# Proximity_module.net
KiCad netlist of a schematic drawn in EAGLE
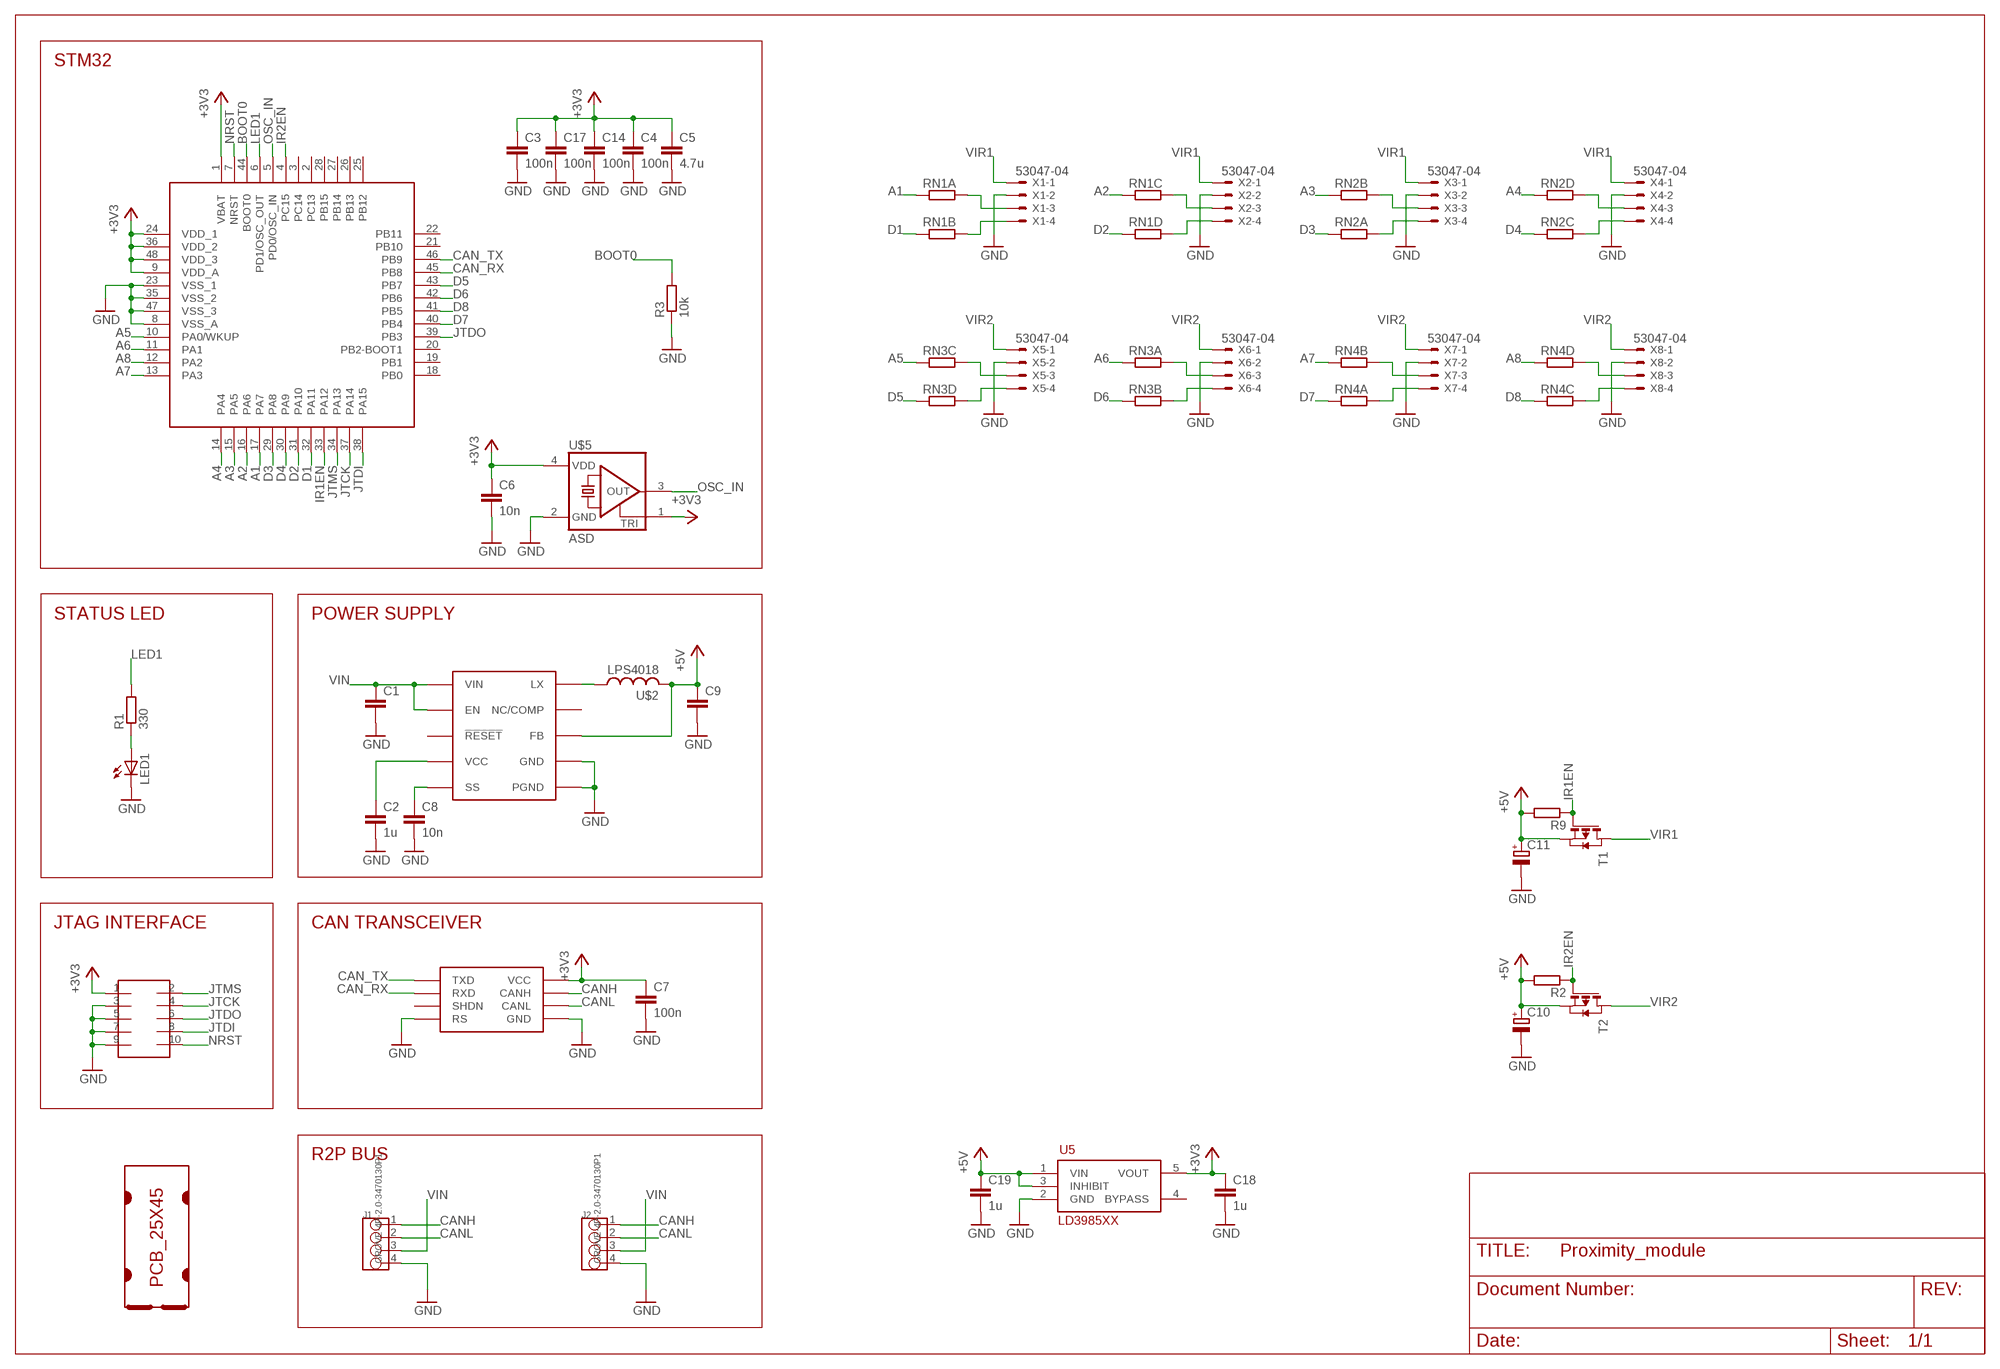
[diagram p0: schematic, sheet 1]

(export (version "E")
  (design (tool "Eeschema 10.0.6"))
  (components
    (comp (ref "C1")
      (value "C-EUC1206")
      (footprint "eagle-import:C1206")
      (libsource (lib "eagle-import") (part "C-EUC1206"))
    )
    (comp (ref "C2")
      (value "1u")
      (footprint "eagle-import:C0603")
      (libsource (lib "eagle-import") (part "C-EUC0603"))
    )
    (comp (ref "C3")
      (value "100n")
      (footprint "eagle-import:C0603")
      (libsource (lib "eagle-import") (part "C-EUC0603"))
    )
    (comp (ref "C4")
      (value "100n")
      (footprint "eagle-import:C0603")
      (libsource (lib "eagle-import") (part "C-EUC0603"))
    )
    (comp (ref "C5")
      (value "4.7u")
      (footprint "eagle-import:C0805")
      (libsource (lib "eagle-import") (part "C-EUC0805"))
    )
    (comp (ref "C6")
      (value "10n")
      (footprint "eagle-import:C0603")
      (libsource (lib "eagle-import") (part "C-EUC0603"))
    )
    (comp (ref "C7")
      (value "100n")
      (footprint "eagle-import:C0603")
      (libsource (lib "eagle-import") (part "C-EUC0603"))
    )
    (comp (ref "C8")
      (value "10n")
      (footprint "eagle-import:C0603")
      (libsource (lib "eagle-import") (part "C-EUC0603"))
    )
    (comp (ref "C9")
      (value "C-EUC0805")
      (footprint "eagle-import:C0805")
      (libsource (lib "eagle-import") (part "C-EUC0805"))
    )
    (comp (ref "C10")
      (value "CPOL-EUB/3528-21R")
      (footprint "eagle-import:B_3528-21R")
      (libsource (lib "eagle-import") (part "CPOL-EUB/3528-21R"))
    )
    (comp (ref "C11")
      (value "CPOL-EUB/3528-21R")
      (footprint "eagle-import:B_3528-21R")
      (libsource (lib "eagle-import") (part "CPOL-EUB/3528-21R"))
    )
    (comp (ref "C14")
      (value "100n")
      (footprint "eagle-import:C0603")
      (libsource (lib "eagle-import") (part "C-EUC0603"))
    )
    (comp (ref "C17")
      (value "100n")
      (footprint "eagle-import:C0603")
      (libsource (lib "eagle-import") (part "C-EUC0603"))
    )
    (comp (ref "C18")
      (value "1u")
      (footprint "eagle-import:C0603")
      (libsource (lib "eagle-import") (part "C-EUC0603"))
    )
    (comp (ref "C19")
      (value "1u")
      (footprint "eagle-import:C0603")
      (libsource (lib "eagle-import") (part "C-EUC0603"))
    )
    (comp (ref "J1")
      (value "GROVE-4P-2.0-3470130P1")
      (footprint "eagle-import:4P-2.0")
      (libsource (lib "eagle-import") (part "GROVE-4P-2.0-3470130P1"))
    )
    (comp (ref "J2")
      (value "GROVE-4P-2.0-3470130P1")
      (footprint "eagle-import:4P-2.0")
      (libsource (lib "eagle-import") (part "GROVE-4P-2.0-3470130P1"))
    )
    (comp (ref "LED1")
      (value "LEDCHIPLED_0805")
      (footprint "eagle-import:CHIPLED_0805")
      (libsource (lib "eagle-import") (part "LEDCHIPLED_0805"))
    )
    (comp (ref "R1")
      (value "330")
      (footprint "eagle-import:R0603")
      (libsource (lib "eagle-import") (part "R-EU_R0603"))
    )
    (comp (ref "R2")
      (value "R-EU_R0603")
      (footprint "eagle-import:R0603")
      (libsource (lib "eagle-import") (part "R-EU_R0603"))
    )
    (comp (ref "R3")
      (value "10k")
      (footprint "eagle-import:R0603")
      (libsource (lib "eagle-import") (part "R-EU_R0603"))
    )
    (comp (ref "R9")
      (value "R-EU_R0603")
      (footprint "eagle-import:R0603")
      (libsource (lib "eagle-import") (part "R-EU_R0603"))
    )
    (comp (ref "RN1")
      (value "RESISTOR_ARRAY_4")
      (footprint "eagle-import:RN8P-4R-CRA06S")
      (libsource (lib "eagle-import") (part "RESISTOR_ARRAY_4"))
    )
    (comp (ref "RN2")
      (value "RESISTOR_ARRAY_4")
      (footprint "eagle-import:RN8P-4R-CRA06S")
      (libsource (lib "eagle-import") (part "RESISTOR_ARRAY_4"))
    )
    (comp (ref "RN3")
      (value "RESISTOR_ARRAY_4")
      (footprint "eagle-import:RN8P-4R-CRA06S")
      (libsource (lib "eagle-import") (part "RESISTOR_ARRAY_4"))
    )
    (comp (ref "RN4")
      (value "RESISTOR_ARRAY_4")
      (footprint "eagle-import:RN8P-4R-CRA06S")
      (libsource (lib "eagle-import") (part "RESISTOR_ARRAY_4"))
    )
    (comp (ref "SOT1")
      (value "MAX3051EKA")
      (footprint "eagle-import:SOT23-8L")
      (libsource (lib "eagle-import") (part "MAX3051EKA"))
    )
    (comp (ref "T1")
      (value "PMOSSOT23")
      (footprint "eagle-import:SOT-23")
      (libsource (lib "eagle-import") (part "PMOSSOT23"))
    )
    (comp (ref "T2")
      (value "PMOSSOT23")
      (footprint "eagle-import:SOT-23")
      (libsource (lib "eagle-import") (part "PMOSSOT23"))
    )
    (comp (ref "U$1")
      (value "PCB_25X45")
      (footprint "eagle-import:25X45")
      (libsource (lib "eagle-import") (part "PCB_25X45"))
    )
    (comp (ref "U$2")
      (value "LPS4018")
      (footprint "eagle-import:LPS4018")
      (libsource (lib "eagle-import") (part "LPS4018"))
    )
    (comp (ref "U$3")
      (value "MAX17501")
      (footprint "eagle-import:TDFN-10")
      (libsource (lib "eagle-import") (part "MAX17501"))
    )
    (comp (ref "U$4")
      (value "FTSH-105TH")
      (footprint "eagle-import:FTSH-105-TH")
      (libsource (lib "eagle-import") (part "FTSH-105TH"))
    )
    (comp (ref "U$5")
      (value "ASD")
      (footprint "eagle-import:2.5X2")
      (libsource (lib "eagle-import") (part "ASD"))
    )
    (comp (ref "U$6")
      (value "STM32F103CXTX")
      (footprint "eagle-import:LQFP48")
      (libsource (lib "eagle-import") (part "STM32F103CXTX"))
    )
    (comp (ref "U5")
      (value "LD3985XX")
      (footprint "eagle-import:SOT23-5L")
      (libsource (lib "eagle-import") (part "LD3985XX"))
    )
    (comp (ref "X1")
      (value "53047-04")
      (footprint "eagle-import:53047-04")
      (fields (field (name "MF") "WALDOM/MOLEX") (field (name "MPN") "53047-0410"))
      (libsource (lib "eagle-import") (part "53?-04047"))
    )
    (comp (ref "X2")
      (value "53047-04")
      (footprint "eagle-import:53047-04")
      (fields (field (name "MF") "WALDOM/MOLEX") (field (name "MPN") "53047-0410"))
      (libsource (lib "eagle-import") (part "53?-04047"))
    )
    (comp (ref "X3")
      (value "53047-04")
      (footprint "eagle-import:53047-04")
      (fields (field (name "MF") "WALDOM/MOLEX") (field (name "MPN") "53047-0410"))
      (libsource (lib "eagle-import") (part "53?-04047"))
    )
    (comp (ref "X4")
      (value "53047-04")
      (footprint "eagle-import:53047-04")
      (fields (field (name "MF") "WALDOM/MOLEX") (field (name "MPN") "53047-0410"))
      (libsource (lib "eagle-import") (part "53?-04047"))
    )
    (comp (ref "X5")
      (value "53047-04")
      (footprint "eagle-import:53047-04")
      (fields (field (name "MF") "WALDOM/MOLEX") (field (name "MPN") "53047-0410"))
      (libsource (lib "eagle-import") (part "53?-04047"))
    )
    (comp (ref "X6")
      (value "53047-04")
      (footprint "eagle-import:53047-04")
      (fields (field (name "MF") "WALDOM/MOLEX") (field (name "MPN") "53047-0410"))
      (libsource (lib "eagle-import") (part "53?-04047"))
    )
    (comp (ref "X7")
      (value "53047-04")
      (footprint "eagle-import:53047-04")
      (fields (field (name "MF") "WALDOM/MOLEX") (field (name "MPN") "53047-0410"))
      (libsource (lib "eagle-import") (part "53?-04047"))
    )
    (comp (ref "X8")
      (value "53047-04")
      (footprint "eagle-import:53047-04")
      (fields (field (name "MF") "WALDOM/MOLEX") (field (name "MPN") "53047-0410"))
      (libsource (lib "eagle-import") (part "53?-04047"))
    )
  )
  (nets
    (net (code "1") (name "+3V3") (class "Default")
      (node (ref "C14") (pin "1") (pinfunction "1_1") (pintype "passive"))
      (node (ref "C17") (pin "1") (pinfunction "1_1") (pintype "passive"))
      (node (ref "C18") (pin "1") (pinfunction "1_1") (pintype "passive"))
      (node (ref "C3") (pin "1") (pinfunction "1_1") (pintype "passive"))
      (node (ref "C4") (pin "1") (pinfunction "1_1") (pintype "passive"))
      (node (ref "C5") (pin "1") (pinfunction "1_1") (pintype "passive"))
      (node (ref "C6") (pin "1") (pinfunction "1_1") (pintype "passive"))
      (node (ref "C7") (pin "1") (pinfunction "1_1") (pintype "passive"))
      (node (ref "SOT1") (pin "3") (pinfunction "VCC_3") (pintype "bidirectional"))
      (node (ref "U$4") (pin "1") (pinfunction "P$1_1") (pintype "bidirectional"))
      (node (ref "U$5") (pin "1") (pinfunction "TRI_1") (pintype "input"))
      (node (ref "U$5") (pin "4") (pinfunction "VDD_4") (pintype "power_in"))
      (node (ref "U$6") (pin "1") (pinfunction "VBAT_1") (pintype "bidirectional"))
      (node (ref "U$6") (pin "24") (pinfunction "VDD_1_24") (pintype "bidirectional"))
      (node (ref "U$6") (pin "36") (pinfunction "VDD_2_36") (pintype "bidirectional"))
      (node (ref "U$6") (pin "48") (pinfunction "VDD_3_48") (pintype "bidirectional"))
      (node (ref "U$6") (pin "9") (pinfunction "VDD_A_9") (pintype "bidirectional"))
      (node (ref "U5") (pin "5") (pinfunction "VOUT_5") (pintype "bidirectional"))
    )
    (net (code "2") (name "+5V") (class "Default")
      (node (ref "C10") (pin "+") (pinfunction "+_+") (pintype "passive"))
      (node (ref "C11") (pin "+") (pinfunction "+_+") (pintype "passive"))
      (node (ref "C19") (pin "1") (pinfunction "1_1") (pintype "passive"))
      (node (ref "C9") (pin "1") (pinfunction "1_1") (pintype "passive"))
      (node (ref "R2") (pin "2") (pinfunction "2_2") (pintype "passive"))
      (node (ref "R9") (pin "2") (pinfunction "2_2") (pintype "passive"))
      (node (ref "T1") (pin "2") (pinfunction "S_2") (pintype "passive"))
      (node (ref "T2") (pin "2") (pinfunction "S_2") (pintype "passive"))
      (node (ref "U$2") (pin "P$2") (pinfunction "2_P$2") (pintype "passive"))
      (node (ref "U$3") (pin "P$5") (pinfunction "FB_P$5") (pintype "bidirectional"))
      (node (ref "U5") (pin "1") (pinfunction "VIN_1") (pintype "bidirectional"))
      (node (ref "U5") (pin "3") (pinfunction "INHIBIT_3") (pintype "bidirectional"))
    )
    (net (code "3") (name "/A1") (class "Default")
      (node (ref "RN1") (pin "1") (pinfunction "1_1") (pintype "passive"))
      (node (ref "U$6") (pin "17") (pinfunction "PA7_17") (pintype "bidirectional"))
    )
    (net (code "4") (name "/A2") (class "Default")
      (node (ref "RN1") (pin "3") (pinfunction "1_3") (pintype "passive"))
      (node (ref "U$6") (pin "16") (pinfunction "PA6_16") (pintype "bidirectional"))
    )
    (net (code "5") (name "/A3") (class "Default")
      (node (ref "RN2") (pin "2") (pinfunction "1_2") (pintype "passive"))
      (node (ref "U$6") (pin "15") (pinfunction "PA5_15") (pintype "bidirectional"))
    )
    (net (code "6") (name "/A4") (class "Default")
      (node (ref "RN2") (pin "4") (pinfunction "1_4") (pintype "passive"))
      (node (ref "U$6") (pin "14") (pinfunction "PA4_14") (pintype "bidirectional"))
    )
    (net (code "7") (name "/A5") (class "Default")
      (node (ref "RN3") (pin "3") (pinfunction "1_3") (pintype "passive"))
      (node (ref "U$6") (pin "10") (pinfunction "PA0/WKUP_10") (pintype "bidirectional"))
    )
    (net (code "8") (name "/A6") (class "Default")
      (node (ref "RN3") (pin "1") (pinfunction "1_1") (pintype "passive"))
      (node (ref "U$6") (pin "11") (pinfunction "PA1_11") (pintype "bidirectional"))
    )
    (net (code "9") (name "/A7") (class "Default")
      (node (ref "RN4") (pin "2") (pinfunction "1_2") (pintype "passive"))
      (node (ref "U$6") (pin "13") (pinfunction "PA3_13") (pintype "bidirectional"))
    )
    (net (code "10") (name "/A8") (class "Default")
      (node (ref "RN4") (pin "4") (pinfunction "1_4") (pintype "passive"))
      (node (ref "U$6") (pin "12") (pinfunction "PA2_12") (pintype "bidirectional"))
    )
    (net (code "11") (name "/BOOT0") (class "Default")
      (node (ref "R3") (pin "2") (pinfunction "2_2") (pintype "passive"))
      (node (ref "U$6") (pin "44") (pinfunction "BOOT0_44") (pintype "bidirectional"))
    )
    (net (code "12") (name "/CANH") (class "Default")
      (node (ref "J1") (pin "1") (pinfunction "1_1") (pintype "bidirectional"))
      (node (ref "J2") (pin "1") (pinfunction "1_1") (pintype "bidirectional"))
      (node (ref "SOT1") (pin "7") (pinfunction "CANH_7") (pintype "bidirectional"))
    )
    (net (code "13") (name "/CANL") (class "Default")
      (node (ref "J1") (pin "2") (pinfunction "2_2") (pintype "bidirectional"))
      (node (ref "J2") (pin "2") (pinfunction "2_2") (pintype "bidirectional"))
      (node (ref "SOT1") (pin "6") (pinfunction "CANL_6") (pintype "bidirectional"))
    )
    (net (code "14") (name "/CAN_RX") (class "Default")
      (node (ref "SOT1") (pin "4") (pinfunction "RXD_4") (pintype "bidirectional"))
      (node (ref "U$6") (pin "45") (pinfunction "PB8_45") (pintype "bidirectional"))
    )
    (net (code "15") (name "/CAN_TX") (class "Default")
      (node (ref "SOT1") (pin "1") (pinfunction "TXD_1") (pintype "bidirectional"))
      (node (ref "U$6") (pin "46") (pinfunction "PB9_46") (pintype "bidirectional"))
    )
    (net (code "16") (name "/D1") (class "Default")
      (node (ref "RN1") (pin "2") (pinfunction "1_2") (pintype "passive"))
      (node (ref "U$6") (pin "32") (pinfunction "PA11_32") (pintype "bidirectional"))
    )
    (net (code "17") (name "/D2") (class "Default")
      (node (ref "RN1") (pin "4") (pinfunction "1_4") (pintype "passive"))
      (node (ref "U$6") (pin "31") (pinfunction "PA10_31") (pintype "bidirectional"))
    )
    (net (code "18") (name "/D3") (class "Default")
      (node (ref "RN2") (pin "1") (pinfunction "1_1") (pintype "passive"))
      (node (ref "U$6") (pin "29") (pinfunction "PA8_29") (pintype "bidirectional"))
    )
    (net (code "19") (name "/D4") (class "Default")
      (node (ref "RN2") (pin "3") (pinfunction "1_3") (pintype "passive"))
      (node (ref "U$6") (pin "30") (pinfunction "PA9_30") (pintype "bidirectional"))
    )
    (net (code "20") (name "/D5") (class "Default")
      (node (ref "RN3") (pin "4") (pinfunction "1_4") (pintype "passive"))
      (node (ref "U$6") (pin "43") (pinfunction "PB7_43") (pintype "bidirectional"))
    )
    (net (code "21") (name "/D6") (class "Default")
      (node (ref "RN3") (pin "2") (pinfunction "1_2") (pintype "passive"))
      (node (ref "U$6") (pin "42") (pinfunction "PB6_42") (pintype "bidirectional"))
    )
    (net (code "22") (name "/D7") (class "Default")
      (node (ref "RN4") (pin "1") (pinfunction "1_1") (pintype "passive"))
      (node (ref "U$6") (pin "40") (pinfunction "PB4_40") (pintype "bidirectional"))
    )
    (net (code "23") (name "/D8") (class "Default")
      (node (ref "RN4") (pin "3") (pinfunction "1_3") (pintype "passive"))
      (node (ref "U$6") (pin "41") (pinfunction "PB5_41") (pintype "bidirectional"))
    )
    (net (code "24") (name "/IR1EN") (class "Default")
      (node (ref "R9") (pin "1") (pinfunction "1_1") (pintype "passive"))
      (node (ref "T1") (pin "3") (pinfunction "G_3") (pintype "passive"))
      (node (ref "U$6") (pin "33") (pinfunction "PA12_33") (pintype "bidirectional"))
    )
    (net (code "25") (name "/IR2EN") (class "Default")
      (node (ref "R2") (pin "1") (pinfunction "1_1") (pintype "passive"))
      (node (ref "T2") (pin "3") (pinfunction "G_3") (pintype "passive"))
      (node (ref "U$6") (pin "4") (pinfunction "PC15_4") (pintype "bidirectional"))
    )
    (net (code "26") (name "/JTCK") (class "Default")
      (node (ref "U$4") (pin "4") (pinfunction "P$4_4") (pintype "bidirectional"))
      (node (ref "U$6") (pin "37") (pinfunction "PA14_37") (pintype "bidirectional"))
    )
    (net (code "27") (name "/JTDI") (class "Default")
      (node (ref "U$4") (pin "8") (pinfunction "P$8_8") (pintype "bidirectional"))
      (node (ref "U$6") (pin "38") (pinfunction "PA15_38") (pintype "bidirectional"))
    )
    (net (code "28") (name "/JTDO") (class "Default")
      (node (ref "U$4") (pin "6") (pinfunction "P$6_6") (pintype "bidirectional"))
      (node (ref "U$6") (pin "39") (pinfunction "PB3_39") (pintype "bidirectional"))
    )
    (net (code "29") (name "/JTMS") (class "Default")
      (node (ref "U$4") (pin "2") (pinfunction "P$2_2") (pintype "bidirectional"))
      (node (ref "U$6") (pin "34") (pinfunction "PA13_34") (pintype "bidirectional"))
    )
    (net (code "30") (name "/LED1") (class "Default")
      (node (ref "R1") (pin "2") (pinfunction "2_2") (pintype "passive"))
      (node (ref "U$6") (pin "6") (pinfunction "PD1/OSC_OUT_6") (pintype "bidirectional"))
    )
    (net (code "31") (name "/NRST") (class "Default")
      (node (ref "U$4") (pin "10") (pinfunction "P$10_10") (pintype "bidirectional"))
      (node (ref "U$6") (pin "7") (pinfunction "NRST_7") (pintype "bidirectional"))
    )
    (net (code "32") (name "/OSC_IN") (class "Default")
      (node (ref "U$5") (pin "3") (pinfunction "OUT_3") (pintype "output"))
      (node (ref "U$6") (pin "5") (pinfunction "PD0/OSC_IN_5") (pintype "bidirectional"))
    )
    (net (code "33") (name "/VIN") (class "Default")
      (node (ref "C1") (pin "1") (pinfunction "1_1") (pintype "passive"))
      (node (ref "J1") (pin "3") (pinfunction "3_3") (pintype "bidirectional"))
      (node (ref "J2") (pin "3") (pinfunction "3_3") (pintype "bidirectional"))
      (node (ref "U$3") (pin "P$2") (pinfunction "VIN_P$2") (pintype "bidirectional"))
      (node (ref "U$3") (pin "P$3") (pinfunction "EN_P$3") (pintype "bidirectional"))
    )
    (net (code "34") (name "/VIR1") (class "Default")
      (node (ref "T1") (pin "1") (pinfunction "D_1") (pintype "passive"))
      (node (ref "X1") (pin "1") (pinfunction "S_1") (pintype "passive"))
      (node (ref "X2") (pin "1") (pinfunction "S_1") (pintype "passive"))
      (node (ref "X3") (pin "1") (pinfunction "S_1") (pintype "passive"))
      (node (ref "X4") (pin "1") (pinfunction "S_1") (pintype "passive"))
    )
    (net (code "35") (name "/VIR2") (class "Default")
      (node (ref "T2") (pin "1") (pinfunction "D_1") (pintype "passive"))
      (node (ref "X5") (pin "1") (pinfunction "S_1") (pintype "passive"))
      (node (ref "X6") (pin "1") (pinfunction "S_1") (pintype "passive"))
      (node (ref "X7") (pin "1") (pinfunction "S_1") (pintype "passive"))
      (node (ref "X8") (pin "1") (pinfunction "S_1") (pintype "passive"))
    )
    (net (code "36") (name "GND") (class "Default")
      (node (ref "C1") (pin "2") (pinfunction "2_2") (pintype "passive"))
      (node (ref "C10") (pin "-") (pinfunction "-_-") (pintype "passive"))
      (node (ref "C11") (pin "-") (pinfunction "-_-") (pintype "passive"))
      (node (ref "C14") (pin "2") (pinfunction "2_2") (pintype "passive"))
      (node (ref "C17") (pin "2") (pinfunction "2_2") (pintype "passive"))
      (node (ref "C18") (pin "2") (pinfunction "2_2") (pintype "passive"))
      (node (ref "C19") (pin "2") (pinfunction "2_2") (pintype "passive"))
      (node (ref "C2") (pin "2") (pinfunction "2_2") (pintype "passive"))
      (node (ref "C3") (pin "2") (pinfunction "2_2") (pintype "passive"))
      (node (ref "C4") (pin "2") (pinfunction "2_2") (pintype "passive"))
      (node (ref "C5") (pin "2") (pinfunction "2_2") (pintype "passive"))
      (node (ref "C6") (pin "2") (pinfunction "2_2") (pintype "passive"))
      (node (ref "C7") (pin "2") (pinfunction "2_2") (pintype "passive"))
      (node (ref "C8") (pin "2") (pinfunction "2_2") (pintype "passive"))
      (node (ref "C9") (pin "2") (pinfunction "2_2") (pintype "passive"))
      (node (ref "J1") (pin "4") (pinfunction "4_4") (pintype "bidirectional"))
      (node (ref "J2") (pin "4") (pinfunction "4_4") (pintype "bidirectional"))
      (node (ref "LED1") (pin "C") (pinfunction "C_C") (pintype "passive"))
      (node (ref "R3") (pin "1") (pinfunction "1_1") (pintype "passive"))
      (node (ref "SOT1") (pin "2") (pinfunction "GND_2") (pintype "bidirectional"))
      (node (ref "SOT1") (pin "8") (pinfunction "RS_8") (pintype "bidirectional"))
      (node (ref "U$3") (pin "P$1") (pinfunction "PGND_P$1") (pintype "bidirectional"))
      (node (ref "U$3") (pin "P$11") (pinfunction "PGND_P$11") (pintype "bidirectional"))
      (node (ref "U$3") (pin "P$9") (pinfunction "GND_P$9") (pintype "bidirectional"))
      (node (ref "U$4") (pin "3") (pinfunction "P$3_3") (pintype "bidirectional"))
      (node (ref "U$4") (pin "5") (pinfunction "P$5_5") (pintype "bidirectional"))
      (node (ref "U$4") (pin "7") (pinfunction "P$7_7") (pintype "bidirectional"))
      (node (ref "U$4") (pin "9") (pinfunction "P$9_9") (pintype "bidirectional"))
      (node (ref "U$5") (pin "2") (pinfunction "GND_2") (pintype "power_in"))
      (node (ref "U$6") (pin "23") (pinfunction "VSS_1_23") (pintype "bidirectional"))
      (node (ref "U$6") (pin "35") (pinfunction "VSS_2_35") (pintype "bidirectional"))
      (node (ref "U$6") (pin "47") (pinfunction "VSS_3_47") (pintype "bidirectional"))
      (node (ref "U$6") (pin "8") (pinfunction "VSS_A_8") (pintype "bidirectional"))
      (node (ref "U5") (pin "2") (pinfunction "GND_2") (pintype "bidirectional"))
      (node (ref "X1") (pin "2") (pinfunction "S_2") (pintype "passive"))
      (node (ref "X2") (pin "2") (pinfunction "S_2") (pintype "passive"))
      (node (ref "X3") (pin "2") (pinfunction "S_2") (pintype "passive"))
      (node (ref "X4") (pin "2") (pinfunction "S_2") (pintype "passive"))
      (node (ref "X5") (pin "2") (pinfunction "S_2") (pintype "passive"))
      (node (ref "X6") (pin "2") (pinfunction "S_2") (pintype "passive"))
      (node (ref "X7") (pin "2") (pinfunction "S_2") (pintype "passive"))
      (node (ref "X8") (pin "2") (pinfunction "S_2") (pintype "passive"))
    )
    (net (code "37") (name "Net-(LED1-PadA)") (class "Default")
      (node (ref "LED1") (pin "A") (pinfunction "A_A") (pintype "passive"))
      (node (ref "R1") (pin "1") (pinfunction "1_1") (pintype "passive"))
    )
    (net (code "38") (name "Net-(RN1A-2)") (class "Default")
      (node (ref "RN1") (pin "8") (pinfunction "2_8") (pintype "passive"))
      (node (ref "X1") (pin "3") (pinfunction "S_3") (pintype "passive"))
    )
    (net (code "39") (name "Net-(RN1B-2)") (class "Default")
      (node (ref "RN1") (pin "7") (pinfunction "2_7") (pintype "passive"))
      (node (ref "X1") (pin "4") (pinfunction "S_4") (pintype "passive"))
    )
    (net (code "40") (name "Net-(RN1C-2)") (class "Default")
      (node (ref "RN1") (pin "6") (pinfunction "2_6") (pintype "passive"))
      (node (ref "X2") (pin "3") (pinfunction "S_3") (pintype "passive"))
    )
    (net (code "41") (name "Net-(RN1D-2)") (class "Default")
      (node (ref "RN1") (pin "5") (pinfunction "2_5") (pintype "passive"))
      (node (ref "X2") (pin "4") (pinfunction "S_4") (pintype "passive"))
    )
    (net (code "42") (name "Net-(RN2A-2)") (class "Default")
      (node (ref "RN2") (pin "8") (pinfunction "2_8") (pintype "passive"))
      (node (ref "X3") (pin "4") (pinfunction "S_4") (pintype "passive"))
    )
    (net (code "43") (name "Net-(RN2B-2)") (class "Default")
      (node (ref "RN2") (pin "7") (pinfunction "2_7") (pintype "passive"))
      (node (ref "X3") (pin "3") (pinfunction "S_3") (pintype "passive"))
    )
    (net (code "44") (name "Net-(RN2C-2)") (class "Default")
      (node (ref "RN2") (pin "6") (pinfunction "2_6") (pintype "passive"))
      (node (ref "X4") (pin "4") (pinfunction "S_4") (pintype "passive"))
    )
    (net (code "45") (name "Net-(RN2D-2)") (class "Default")
      (node (ref "RN2") (pin "5") (pinfunction "2_5") (pintype "passive"))
      (node (ref "X4") (pin "3") (pinfunction "S_3") (pintype "passive"))
    )
    (net (code "46") (name "Net-(RN3A-2)") (class "Default")
      (node (ref "RN3") (pin "8") (pinfunction "2_8") (pintype "passive"))
      (node (ref "X6") (pin "3") (pinfunction "S_3") (pintype "passive"))
    )
    (net (code "47") (name "Net-(RN3B-2)") (class "Default")
      (node (ref "RN3") (pin "7") (pinfunction "2_7") (pintype "passive"))
      (node (ref "X6") (pin "4") (pinfunction "S_4") (pintype "passive"))
    )
    (net (code "48") (name "Net-(RN3C-2)") (class "Default")
      (node (ref "RN3") (pin "6") (pinfunction "2_6") (pintype "passive"))
      (node (ref "X5") (pin "3") (pinfunction "S_3") (pintype "passive"))
    )
    (net (code "49") (name "Net-(RN3D-2)") (class "Default")
      (node (ref "RN3") (pin "5") (pinfunction "2_5") (pintype "passive"))
      (node (ref "X5") (pin "4") (pinfunction "S_4") (pintype "passive"))
    )
    (net (code "50") (name "Net-(RN4A-2)") (class "Default")
      (node (ref "RN4") (pin "8") (pinfunction "2_8") (pintype "passive"))
      (node (ref "X7") (pin "4") (pinfunction "S_4") (pintype "passive"))
    )
    (net (code "51") (name "Net-(RN4B-2)") (class "Default")
      (node (ref "RN4") (pin "7") (pinfunction "2_7") (pintype "passive"))
      (node (ref "X7") (pin "3") (pinfunction "S_3") (pintype "passive"))
    )
    (net (code "52") (name "Net-(RN4C-2)") (class "Default")
      (node (ref "RN4") (pin "6") (pinfunction "2_6") (pintype "passive"))
      (node (ref "X8") (pin "4") (pinfunction "S_4") (pintype "passive"))
    )
    (net (code "53") (name "Net-(RN4D-2)") (class "Default")
      (node (ref "RN4") (pin "5") (pinfunction "2_5") (pintype "passive"))
      (node (ref "X8") (pin "3") (pinfunction "S_3") (pintype "passive"))
    )
    (net (code "54") (name "Net-(U$2-1)") (class "Default")
      (node (ref "U$2") (pin "P$1") (pinfunction "1_P$1") (pintype "passive"))
      (node (ref "U$3") (pin "P$10") (pinfunction "LX_P$10") (pintype "bidirectional"))
    )
    (net (code "55") (name "Net-(U$3-SS)") (class "Default")
      (node (ref "C8") (pin "1") (pinfunction "1_1") (pintype "passive"))
      (node (ref "U$3") (pin "P$6") (pinfunction "SS_P$6") (pintype "bidirectional"))
    )
    (net (code "56") (name "Net-(U$3-VCC)") (class "Default")
      (node (ref "C2") (pin "1") (pinfunction "1_1") (pintype "passive"))
      (node (ref "U$3") (pin "P$4") (pinfunction "VCC_P$4") (pintype "bidirectional"))
    )
    (net (code "57") (name "unconnected-(SOT1-SHDN-Pad5)") (class "Default")
      (node (ref "SOT1") (pin "5") (pinfunction "SHDN_5") (pintype "bidirectional"))
    )
    (net (code "58") (name "unconnected-(U$3-NC{slash}COMP-PadP$7)") (class "Default")
      (node (ref "U$3") (pin "P$7") (pinfunction "NC/COMP_P$7") (pintype "bidirectional"))
    )
    (net (code "59") (name "unconnected-(U$3-~{RESET}-PadP$8)") (class "Default")
      (node (ref "U$3") (pin "P$8") (pinfunction "~{RESET}_P$8") (pintype "bidirectional"))
    )
    (net (code "60") (name "unconnected-(U$6-PB0-Pad18)") (class "Default")
      (node (ref "U$6") (pin "18") (pinfunction "PB0_18") (pintype "bidirectional"))
    )
    (net (code "61") (name "unconnected-(U$6-PB1-Pad19)") (class "Default")
      (node (ref "U$6") (pin "19") (pinfunction "PB1_19") (pintype "bidirectional"))
    )
    (net (code "62") (name "unconnected-(U$6-PB2-BOOT1-Pad20)") (class "Default")
      (node (ref "U$6") (pin "20") (pinfunction "PB2-BOOT1_20") (pintype "bidirectional"))
    )
    (net (code "63") (name "unconnected-(U$6-PB10-Pad21)") (class "Default")
      (node (ref "U$6") (pin "21") (pinfunction "PB10_21") (pintype "bidirectional"))
    )
    (net (code "64") (name "unconnected-(U$6-PB11-Pad22)") (class "Default")
      (node (ref "U$6") (pin "22") (pinfunction "PB11_22") (pintype "bidirectional"))
    )
    (net (code "65") (name "unconnected-(U$6-PB12-Pad25)") (class "Default")
      (node (ref "U$6") (pin "25") (pinfunction "PB12_25") (pintype "bidirectional"))
    )
    (net (code "66") (name "unconnected-(U$6-PB13-Pad26)") (class "Default")
      (node (ref "U$6") (pin "26") (pinfunction "PB13_26") (pintype "bidirectional"))
    )
    (net (code "67") (name "unconnected-(U$6-PB14-Pad27)") (class "Default")
      (node (ref "U$6") (pin "27") (pinfunction "PB14_27") (pintype "bidirectional"))
    )
    (net (code "68") (name "unconnected-(U$6-PB15-Pad28)") (class "Default")
      (node (ref "U$6") (pin "28") (pinfunction "PB15_28") (pintype "bidirectional"))
    )
    (net (code "69") (name "unconnected-(U$6-PC13-Pad2)") (class "Default")
      (node (ref "U$6") (pin "2") (pinfunction "PC13_2") (pintype "bidirectional"))
    )
    (net (code "70") (name "unconnected-(U$6-PC14-Pad3)") (class "Default")
      (node (ref "U$6") (pin "3") (pinfunction "PC14_3") (pintype "bidirectional"))
    )
    (net (code "71") (name "unconnected-(U5-BYPASS-Pad4)") (class "Default")
      (node (ref "U5") (pin "4") (pinfunction "BYPASS_4") (pintype "bidirectional"))
    )
  )
)
